# canAIReSensor.net
KiCad netlist of a schematic drawn in EAGLE
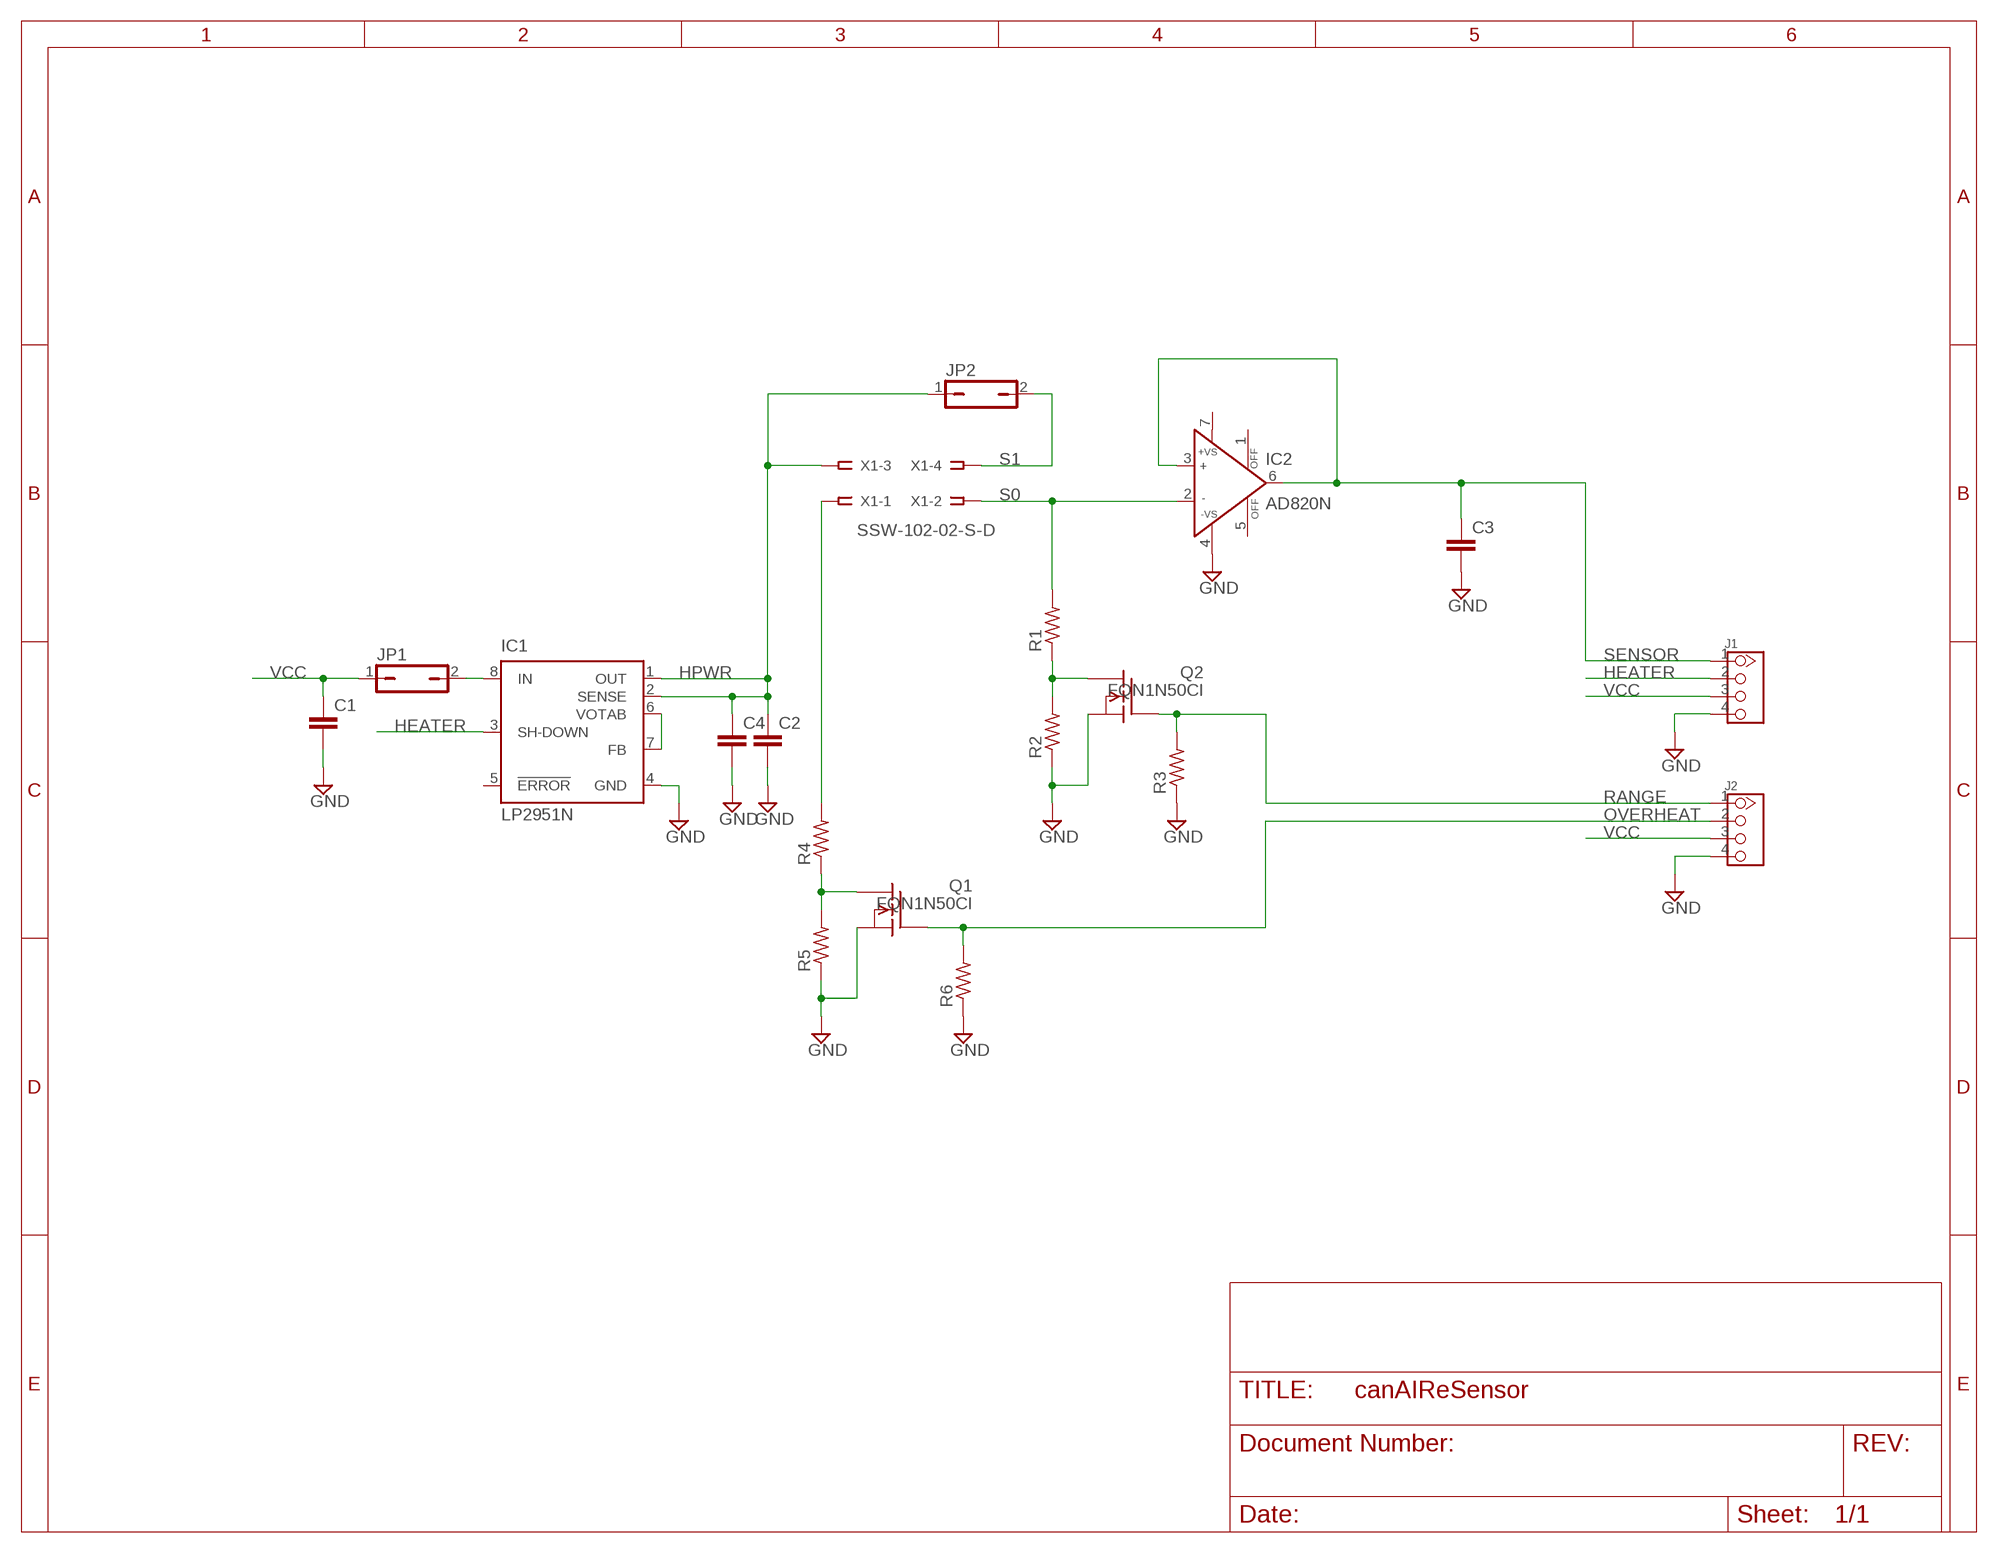
[diagram p0: schematic, sheet 1]

(export (version "E")
  (design (tool "Eeschema 10.0.6"))
  (components
    (comp (ref "C1")
      (value "C-EU050-024X044")
      (footprint "eagle-import:C050-024X044")
      (libsource (lib "eagle-import") (part "C-EU050-024X044"))
    )
    (comp (ref "C2")
      (value "C-EU050-024X044")
      (footprint "eagle-import:C050-024X044")
      (libsource (lib "eagle-import") (part "C-EU050-024X044"))
    )
    (comp (ref "C3")
      (value "C-EU050-024X044")
      (footprint "eagle-import:C050-024X044")
      (libsource (lib "eagle-import") (part "C-EU050-024X044"))
    )
    (comp (ref "C4")
      (value "C-EU050-024X044")
      (footprint "eagle-import:C050-024X044")
      (libsource (lib "eagle-import") (part "C-EU050-024X044"))
    )
    (comp (ref "IC1")
      (value "LP2951N")
      (footprint "eagle-import:DIL08")
      (libsource (lib "eagle-import") (part "LP2951N"))
    )
    (comp (ref "IC2")
      (value "AD820N")
      (footprint "eagle-import:DIL08")
      (libsource (lib "eagle-import") (part "AD820N"))
    )
    (comp (ref "J1")
      (value "TWIG-4P-2.0'90D'")
      (footprint "eagle-import:4P-2.0-90D")
      (libsource (lib "eagle-import") (part "TWIG-4P-2.0'90D'"))
    )
    (comp (ref "J2")
      (value "TWIG-4P-2.0'90D'")
      (footprint "eagle-import:4P-2.0-90D")
      (libsource (lib "eagle-import") (part "TWIG-4P-2.0'90D'"))
    )
    (comp (ref "JP1")
      (value "JP1Q")
      (footprint "eagle-import:JP1")
      (libsource (lib "eagle-import") (part "JP1Q"))
    )
    (comp (ref "JP2")
      (value "JP1Q")
      (footprint "eagle-import:JP1")
      (libsource (lib "eagle-import") (part "JP1Q"))
    )
    (comp (ref "Q1")
      (value "FQN1N50CI")
      (footprint "eagle-import:TO92-INLINE")
      (libsource (lib "eagle-import") (part "FQN1N50CI"))
    )
    (comp (ref "Q2")
      (value "FQN1N50CI")
      (footprint "eagle-import:TO92-INLINE")
      (libsource (lib "eagle-import") (part "FQN1N50CI"))
    )
    (comp (ref "R1")
      (value "R-US_0207/10")
      (footprint "eagle-import:0207_10")
      (libsource (lib "eagle-import") (part "R-US_0207/10"))
    )
    (comp (ref "R2")
      (value "R-US_0207/10")
      (footprint "eagle-import:0207_10")
      (libsource (lib "eagle-import") (part "R-US_0207/10"))
    )
    (comp (ref "R3")
      (value "R-US_0207/10")
      (footprint "eagle-import:0207_10")
      (libsource (lib "eagle-import") (part "R-US_0207/10"))
    )
    (comp (ref "R4")
      (value "R-US_0207/10")
      (footprint "eagle-import:0207_10")
      (libsource (lib "eagle-import") (part "R-US_0207/10"))
    )
    (comp (ref "R5")
      (value "R-US_0207/10")
      (footprint "eagle-import:0207_10")
      (libsource (lib "eagle-import") (part "R-US_0207/10"))
    )
    (comp (ref "R6")
      (value "R-US_0207/10")
      (footprint "eagle-import:0207_10")
      (libsource (lib "eagle-import") (part "R-US_0207/10"))
    )
    (comp (ref "X1")
      (value "SSW-102-02-S-D")
      (footprint "eagle-import:SSW-102-02-S-D")
      (libsource (lib "eagle-import") (part "SSW-102-02-S-D"))
    )
  )
  (nets
    (net (code "1") (name "/HEATER") (class "Default")
      (node (ref "IC1") (pin "3") (pinfunction "SH-DOWN_3") (pintype "input"))
      (node (ref "J1") (pin "2") (pinfunction "2_2") (pintype "bidirectional"))
    )
    (net (code "2") (name "/HPWR") (class "Default")
      (node (ref "C2") (pin "1") (pinfunction "1_1") (pintype "passive"))
      (node (ref "C4") (pin "1") (pinfunction "1_1") (pintype "passive"))
      (node (ref "IC1") (pin "1") (pinfunction "OUT_1") (pintype "input"))
      (node (ref "IC1") (pin "2") (pinfunction "SENSE_2") (pintype "input"))
      (node (ref "JP2") (pin "1") (pinfunction "1_1") (pintype "passive"))
      (node (ref "X1") (pin "3") (pinfunction "1_3") (pintype "passive"))
    )
    (net (code "3") (name "/OVERHEAT") (class "Default")
      (node (ref "J2") (pin "2") (pinfunction "2_2") (pintype "bidirectional"))
      (node (ref "Q1") (pin "2") (pinfunction "G_2") (pintype "passive"))
      (node (ref "R6") (pin "2") (pinfunction "2_2") (pintype "passive"))
    )
    (net (code "4") (name "/RANGE") (class "Default")
      (node (ref "J2") (pin "1") (pinfunction "1_1") (pintype "bidirectional"))
      (node (ref "Q2") (pin "2") (pinfunction "G_2") (pintype "passive"))
      (node (ref "R3") (pin "2") (pinfunction "2_2") (pintype "passive"))
    )
    (net (code "5") (name "/S0") (class "Default")
      (node (ref "IC2") (pin "2") (pinfunction "IN-_2") (pintype "input"))
      (node (ref "R1") (pin "2") (pinfunction "2_2") (pintype "passive"))
      (node (ref "X1") (pin "2") (pinfunction "1_2") (pintype "passive"))
    )
    (net (code "6") (name "/S1") (class "Default")
      (node (ref "JP2") (pin "2") (pinfunction "2_2") (pintype "passive"))
      (node (ref "X1") (pin "4") (pinfunction "1_4") (pintype "passive"))
    )
    (net (code "7") (name "/SENSOR") (class "Default")
      (node (ref "C3") (pin "1") (pinfunction "1_1") (pintype "passive"))
      (node (ref "IC2") (pin "3") (pinfunction "IN+_3") (pintype "input"))
      (node (ref "IC2") (pin "6") (pinfunction "OUT_6") (pintype "output"))
      (node (ref "J1") (pin "1") (pinfunction "1_1") (pintype "bidirectional"))
    )
    (net (code "8") (name "/VCC") (class "Default")
      (node (ref "C1") (pin "1") (pinfunction "1_1") (pintype "passive"))
      (node (ref "J1") (pin "3") (pinfunction "3_3") (pintype "bidirectional"))
      (node (ref "J2") (pin "3") (pinfunction "3_3") (pintype "bidirectional"))
      (node (ref "JP1") (pin "1") (pinfunction "1_1") (pintype "passive"))
    )
    (net (code "9") (name "GND") (class "Default")
      (node (ref "C1") (pin "2") (pinfunction "2_2") (pintype "passive"))
      (node (ref "C2") (pin "2") (pinfunction "2_2") (pintype "passive"))
      (node (ref "C3") (pin "2") (pinfunction "2_2") (pintype "passive"))
      (node (ref "C4") (pin "2") (pinfunction "2_2") (pintype "passive"))
      (node (ref "IC1") (pin "4") (pinfunction "GND_4") (pintype "power_in"))
      (node (ref "IC2") (pin "4") (pinfunction "-VS_4") (pintype "input"))
      (node (ref "J1") (pin "4") (pinfunction "4_4") (pintype "bidirectional"))
      (node (ref "J2") (pin "4") (pinfunction "4_4") (pintype "bidirectional"))
      (node (ref "Q1") (pin "3") (pinfunction "S_3") (pintype "passive"))
      (node (ref "Q2") (pin "3") (pinfunction "S_3") (pintype "passive"))
      (node (ref "R2") (pin "1") (pinfunction "1_1") (pintype "passive"))
      (node (ref "R3") (pin "1") (pinfunction "1_1") (pintype "passive"))
      (node (ref "R5") (pin "1") (pinfunction "1_1") (pintype "passive"))
      (node (ref "R6") (pin "1") (pinfunction "1_1") (pintype "passive"))
    )
    (net (code "10") (name "Net-(IC1-FB)") (class "Default")
      (node (ref "IC1") (pin "6") (pinfunction "VOTAB_6") (pintype "passive"))
      (node (ref "IC1") (pin "7") (pinfunction "FB_7") (pintype "input"))
    )
    (net (code "11") (name "Net-(IC1-IN)") (class "Default")
      (node (ref "IC1") (pin "8") (pinfunction "IN_8") (pintype "input"))
      (node (ref "JP1") (pin "2") (pinfunction "2_2") (pintype "passive"))
    )
    (net (code "12") (name "Net-(Q1-D)") (class "Default")
      (node (ref "Q1") (pin "1") (pinfunction "D_1") (pintype "passive"))
      (node (ref "R4") (pin "1") (pinfunction "1_1") (pintype "passive"))
      (node (ref "R5") (pin "2") (pinfunction "2_2") (pintype "passive"))
    )
    (net (code "13") (name "Net-(Q2-D)") (class "Default")
      (node (ref "Q2") (pin "1") (pinfunction "D_1") (pintype "passive"))
      (node (ref "R1") (pin "1") (pinfunction "1_1") (pintype "passive"))
      (node (ref "R2") (pin "2") (pinfunction "2_2") (pintype "passive"))
    )
    (net (code "14") (name "Net-(R4-Pad2)") (class "Default")
      (node (ref "R4") (pin "2") (pinfunction "2_2") (pintype "passive"))
      (node (ref "X1") (pin "1") (pinfunction "1_1") (pintype "passive"))
    )
    (net (code "15") (name "unconnected-(IC1-~{ERROR}-Pad5)") (class "Default")
      (node (ref "IC1") (pin "5") (pinfunction "~{ERROR}_5") (pintype "output"))
    )
    (net (code "16") (name "unconnected-(IC2-+VS-Pad7)") (class "Default")
      (node (ref "IC2") (pin "7") (pinfunction "+VS_7") (pintype "input"))
    )
    (net (code "17") (name "unconnected-(IC2-OFF-Pad1)") (class "Default")
      (node (ref "IC2") (pin "1") (pinfunction "OFF_1") (pintype "passive"))
    )
    (net (code "18") (name "unconnected-(IC2-OFF-Pad5)") (class "Default")
      (node (ref "IC2") (pin "5") (pinfunction "OFF_5") (pintype "passive"))
    )
  )
)
